# KeypadConnection.net
KiCad netlist of a schematic drawn in Altium Designer
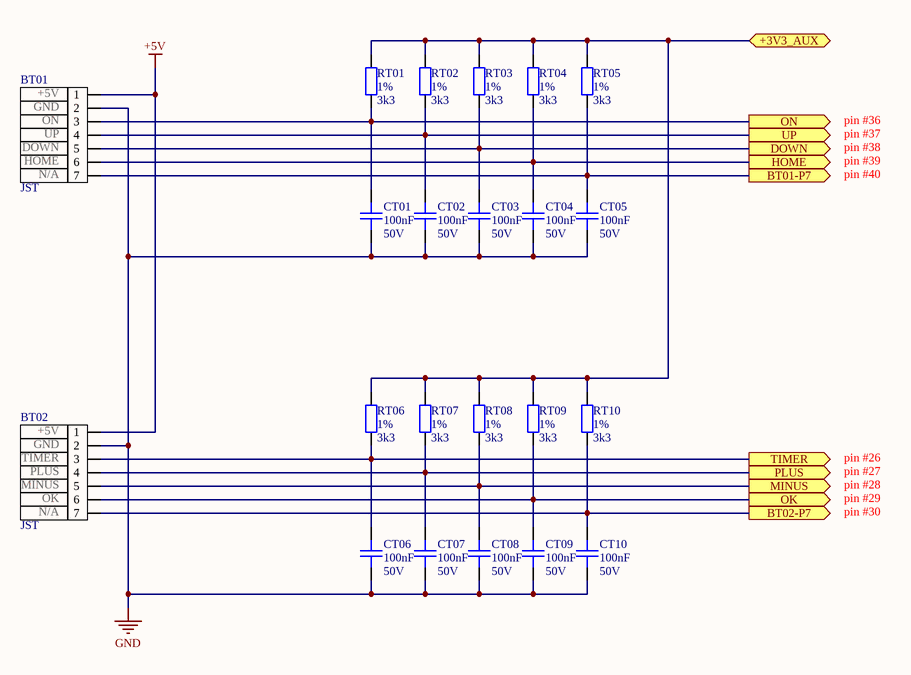
[diagram p0: KeypadConnection.SchDoc]

(export (version "E")
  (design (tool "Eeschema 10.0.6"))
  (components
    (comp (ref "BT01")
      (value "JST")
      (fields
        (field (name "PIN_1") "+5V")
        (field (name "PIN_2") "GND")
        (field (name "PIN_3") "ON")
        (field (name "PIN_4") "UP")
        (field (name "PIN_5") "DOWN")
        (field (name "PIN_6") "HOME")
        (field (name "PIN_7") "N/A")
      )
      (libsource (lib "connectors_ffc") (part "CONN FFC 7POS 1MM"))
    )
    (comp (ref "BT02")
      (value "JST")
      (fields
        (field (name "PIN_1") "+5V")
        (field (name "PIN_2") "GND")
        (field (name "PIN_3") "TIMER")
        (field (name "PIN_4") "PLUS")
        (field (name "PIN_5") "MINUS")
        (field (name "PIN_6") "OK")
        (field (name "PIN_7") "N/A")
      )
      (libsource (lib "connectors_ffc") (part "CONN FFC 7POS 1MM"))
    )
    (comp (ref "CT01")
      (value "CAP CER 0.1uF ±10% 50V X7R 0603")
      (footprint "CAPC1608X08N_0603")
      (description "Capacitor")
      (fields
        (field (name "MANUFACTURER") "KEMET")
        (field (name "MANUFACTURER PART NUMBER") "C0603C104M5RACTU")
        (field (name "CAPACITANCE") "100nF")
        (field (name "VOLTAGE RATING") "50V")
      )
      (libsource (lib "capacitors_smd") (part "CAP CER 0.1uF ±10% 50V X7R 0603"))
    )
    (comp (ref "CT02")
      (value "CAP CER 0.1uF ±10% 50V X7R 0603")
      (footprint "CAPC1608X08N_0603")
      (description "Capacitor")
      (fields
        (field (name "MANUFACTURER") "KEMET")
        (field (name "MANUFACTURER PART NUMBER") "C0603C104M5RACTU")
        (field (name "CAPACITANCE") "100nF")
        (field (name "VOLTAGE RATING") "50V")
      )
      (libsource (lib "capacitors_smd") (part "CAP CER 0.1uF ±10% 50V X7R 0603"))
    )
    (comp (ref "CT03")
      (value "CAP CER 0.1uF ±10% 50V X7R 0603")
      (footprint "CAPC1608X08N_0603")
      (description "Capacitor")
      (fields
        (field (name "MANUFACTURER") "KEMET")
        (field (name "MANUFACTURER PART NUMBER") "C0603C104M5RACTU")
        (field (name "CAPACITANCE") "100nF")
        (field (name "VOLTAGE RATING") "50V")
      )
      (libsource (lib "capacitors_smd") (part "CAP CER 0.1uF ±10% 50V X7R 0603"))
    )
    (comp (ref "CT04")
      (value "CAP CER 0.1uF ±10% 50V X7R 0603")
      (footprint "CAPC1608X08N_0603")
      (description "Capacitor")
      (fields
        (field (name "MANUFACTURER") "KEMET")
        (field (name "MANUFACTURER PART NUMBER") "C0603C104M5RACTU")
        (field (name "CAPACITANCE") "100nF")
        (field (name "VOLTAGE RATING") "50V")
      )
      (libsource (lib "capacitors_smd") (part "CAP CER 0.1uF ±10% 50V X7R 0603"))
    )
    (comp (ref "CT05")
      (value "CAP CER 0.1uF ±10% 50V X7R 0603")
      (footprint "CAPC1608X08N_0603")
      (description "Capacitor")
      (fields
        (field (name "MANUFACTURER") "KEMET")
        (field (name "MANUFACTURER PART NUMBER") "C0603C104M5RACTU")
        (field (name "CAPACITANCE") "100nF")
        (field (name "VOLTAGE RATING") "50V")
      )
      (libsource (lib "capacitors_smd") (part "CAP CER 0.1uF ±10% 50V X7R 0603"))
    )
    (comp (ref "CT06")
      (value "CAP CER 0.1uF ±10% 50V X7R 0603")
      (footprint "CAPC1608X08N_0603")
      (description "Capacitor")
      (fields
        (field (name "MANUFACTURER") "KEMET")
        (field (name "MANUFACTURER PART NUMBER") "C0603C104M5RACTU")
        (field (name "CAPACITANCE") "100nF")
        (field (name "VOLTAGE RATING") "50V")
      )
      (libsource (lib "capacitors_smd") (part "CAP CER 0.1uF ±10% 50V X7R 0603"))
    )
    (comp (ref "CT07")
      (value "CAP CER 0.1uF ±10% 50V X7R 0603")
      (footprint "CAPC1608X08N_0603")
      (description "Capacitor")
      (fields
        (field (name "MANUFACTURER") "KEMET")
        (field (name "MANUFACTURER PART NUMBER") "C0603C104M5RACTU")
        (field (name "CAPACITANCE") "100nF")
        (field (name "VOLTAGE RATING") "50V")
      )
      (libsource (lib "capacitors_smd") (part "CAP CER 0.1uF ±10% 50V X7R 0603"))
    )
    (comp (ref "CT08")
      (value "CAP CER 0.1uF ±10% 50V X7R 0603")
      (footprint "CAPC1608X08N_0603")
      (description "Capacitor")
      (fields
        (field (name "MANUFACTURER") "KEMET")
        (field (name "MANUFACTURER PART NUMBER") "C0603C104M5RACTU")
        (field (name "CAPACITANCE") "100nF")
        (field (name "VOLTAGE RATING") "50V")
      )
      (libsource (lib "capacitors_smd") (part "CAP CER 0.1uF ±10% 50V X7R 0603"))
    )
    (comp (ref "CT09")
      (value "CAP CER 0.1uF ±10% 50V X7R 0603")
      (footprint "CAPC1608X08N_0603")
      (description "Capacitor")
      (fields
        (field (name "MANUFACTURER") "KEMET")
        (field (name "MANUFACTURER PART NUMBER") "C0603C104M5RACTU")
        (field (name "CAPACITANCE") "100nF")
        (field (name "VOLTAGE RATING") "50V")
      )
      (libsource (lib "capacitors_smd") (part "CAP CER 0.1uF ±10% 50V X7R 0603"))
    )
    (comp (ref "CT10")
      (value "CAP CER 0.1uF ±10% 50V X7R 0603")
      (footprint "CAPC1608X08N_0603")
      (description "Capacitor")
      (fields
        (field (name "MANUFACTURER") "KEMET")
        (field (name "MANUFACTURER PART NUMBER") "C0603C104M5RACTU")
        (field (name "CAPACITANCE") "100nF")
        (field (name "VOLTAGE RATING") "50V")
      )
      (libsource (lib "capacitors_smd") (part "CAP CER 0.1uF ±10% 50V X7R 0603"))
    )
    (comp (ref "RT01")
      (value "R 3kΩ ±1% 0603 0.1W")
      (footprint "Resistor-0603")
      (description "Resistor")
      (fields
        (field (name "MANUFACTURER") "Yageo")
        (field (name "MANUFACTURER PART NUMBER") "RC0603FR-073KL")
        (field (name "TOLERANCE") "1%")
        (field (name "RESISTANCE") "3k3")
      )
      (libsource (lib "resistors_smd") (part "R 3kΩ ±1% 0603 0.1W"))
    )
    (comp (ref "RT02")
      (value "R 3kΩ ±1% 0603 0.1W")
      (footprint "Resistor-0603")
      (description "Resistor")
      (fields
        (field (name "MANUFACTURER") "Yageo")
        (field (name "MANUFACTURER PART NUMBER") "RC0603FR-073KL")
        (field (name "TOLERANCE") "1%")
        (field (name "RESISTANCE") "3k3")
      )
      (libsource (lib "resistors_smd") (part "R 3kΩ ±1% 0603 0.1W"))
    )
    (comp (ref "RT03")
      (value "R 3kΩ ±1% 0603 0.1W")
      (footprint "Resistor-0603")
      (description "Resistor")
      (fields
        (field (name "MANUFACTURER") "Yageo")
        (field (name "MANUFACTURER PART NUMBER") "RC0603FR-073KL")
        (field (name "TOLERANCE") "1%")
        (field (name "RESISTANCE") "3k3")
      )
      (libsource (lib "resistors_smd") (part "R 3kΩ ±1% 0603 0.1W"))
    )
    (comp (ref "RT04")
      (value "R 3kΩ ±1% 0603 0.1W")
      (footprint "Resistor-0603")
      (description "Resistor")
      (fields
        (field (name "MANUFACTURER") "Yageo")
        (field (name "MANUFACTURER PART NUMBER") "RC0603FR-073KL")
        (field (name "TOLERANCE") "1%")
        (field (name "RESISTANCE") "3k3")
      )
      (libsource (lib "resistors_smd") (part "R 3kΩ ±1% 0603 0.1W"))
    )
    (comp (ref "RT05")
      (value "R 3kΩ ±1% 0603 0.1W")
      (footprint "Resistor-0603")
      (description "Resistor")
      (fields
        (field (name "MANUFACTURER") "Yageo")
        (field (name "MANUFACTURER PART NUMBER") "RC0603FR-073KL")
        (field (name "TOLERANCE") "1%")
        (field (name "RESISTANCE") "3k3")
      )
      (libsource (lib "resistors_smd") (part "R 3kΩ ±1% 0603 0.1W"))
    )
    (comp (ref "RT06")
      (value "R 3kΩ ±1% 0603 0.1W")
      (footprint "Resistor-0603")
      (description "Resistor")
      (fields
        (field (name "MANUFACTURER") "Yageo")
        (field (name "MANUFACTURER PART NUMBER") "RC0603FR-073KL")
        (field (name "TOLERANCE") "1%")
        (field (name "RESISTANCE") "3k3")
      )
      (libsource (lib "resistors_smd") (part "R 3kΩ ±1% 0603 0.1W"))
    )
    (comp (ref "RT07")
      (value "R 3kΩ ±1% 0603 0.1W")
      (footprint "Resistor-0603")
      (description "Resistor")
      (fields
        (field (name "MANUFACTURER") "Yageo")
        (field (name "MANUFACTURER PART NUMBER") "RC0603FR-073KL")
        (field (name "TOLERANCE") "1%")
        (field (name "RESISTANCE") "3k3")
      )
      (libsource (lib "resistors_smd") (part "R 3kΩ ±1% 0603 0.1W"))
    )
    (comp (ref "RT08")
      (value "R 3kΩ ±1% 0603 0.1W")
      (footprint "Resistor-0603")
      (description "Resistor")
      (fields
        (field (name "MANUFACTURER") "Yageo")
        (field (name "MANUFACTURER PART NUMBER") "RC0603FR-073KL")
        (field (name "TOLERANCE") "1%")
        (field (name "RESISTANCE") "3k3")
      )
      (libsource (lib "resistors_smd") (part "R 3kΩ ±1% 0603 0.1W"))
    )
    (comp (ref "RT09")
      (value "R 3kΩ ±1% 0603 0.1W")
      (footprint "Resistor-0603")
      (description "Resistor")
      (fields
        (field (name "MANUFACTURER") "Yageo")
        (field (name "MANUFACTURER PART NUMBER") "RC0603FR-073KL")
        (field (name "TOLERANCE") "1%")
        (field (name "RESISTANCE") "3k3")
      )
      (libsource (lib "resistors_smd") (part "R 3kΩ ±1% 0603 0.1W"))
    )
    (comp (ref "RT10")
      (value "R 3kΩ ±1% 0603 0.1W")
      (footprint "Resistor-0603")
      (description "Resistor")
      (fields
        (field (name "MANUFACTURER") "Yageo")
        (field (name "MANUFACTURER PART NUMBER") "RC0603FR-073KL")
        (field (name "TOLERANCE") "1%")
        (field (name "RESISTANCE") "3k3")
      )
      (libsource (lib "resistors_smd") (part "R 3kΩ ±1% 0603 0.1W"))
    )
  )
  (nets
    (net (code "1") (name "+5V") (class "Default")
      (node (ref "BT01") (pin "1") (pinfunction "1_1") (pintype "passive"))
      (node (ref "BT02") (pin "1") (pinfunction "1_1") (pintype "passive"))
    )
    (net (code "2") (name "/+3V3_AUX") (class "Default")
      (node (ref "RT01") (pin "2") (pinfunction "2_2") (pintype "passive"))
      (node (ref "RT02") (pin "2") (pinfunction "2_2") (pintype "passive"))
      (node (ref "RT03") (pin "2") (pinfunction "2_2") (pintype "passive"))
      (node (ref "RT04") (pin "2") (pinfunction "2_2") (pintype "passive"))
      (node (ref "RT05") (pin "2") (pinfunction "2_2") (pintype "passive"))
      (node (ref "RT06") (pin "2") (pinfunction "2_2") (pintype "passive"))
      (node (ref "RT07") (pin "2") (pinfunction "2_2") (pintype "passive"))
      (node (ref "RT08") (pin "2") (pinfunction "2_2") (pintype "passive"))
      (node (ref "RT09") (pin "2") (pinfunction "2_2") (pintype "passive"))
      (node (ref "RT10") (pin "2") (pinfunction "2_2") (pintype "passive"))
    )
    (net (code "3") (name "/BT01-P7") (class "Default")
      (node (ref "BT01") (pin "7") (pinfunction "7_7") (pintype "passive"))
      (node (ref "CT05") (pin "2") (pinfunction "2_2") (pintype "passive"))
      (node (ref "RT05") (pin "1") (pinfunction "1_1") (pintype "passive"))
    )
    (net (code "4") (name "/BT02-P7") (class "Default")
      (node (ref "BT02") (pin "7") (pinfunction "7_7") (pintype "passive"))
      (node (ref "CT10") (pin "2") (pinfunction "2_2") (pintype "passive"))
      (node (ref "RT10") (pin "1") (pinfunction "1_1") (pintype "passive"))
    )
    (net (code "5") (name "/DOWN") (class "Default")
      (node (ref "BT01") (pin "5") (pinfunction "5_5") (pintype "passive"))
      (node (ref "CT03") (pin "2") (pinfunction "2_2") (pintype "passive"))
      (node (ref "RT03") (pin "1") (pinfunction "1_1") (pintype "passive"))
    )
    (net (code "6") (name "/HOME") (class "Default")
      (node (ref "BT01") (pin "6") (pinfunction "6_6") (pintype "passive"))
      (node (ref "CT04") (pin "2") (pinfunction "2_2") (pintype "passive"))
      (node (ref "RT04") (pin "1") (pinfunction "1_1") (pintype "passive"))
    )
    (net (code "7") (name "/MINUS") (class "Default")
      (node (ref "BT02") (pin "5") (pinfunction "5_5") (pintype "passive"))
      (node (ref "CT08") (pin "2") (pinfunction "2_2") (pintype "passive"))
      (node (ref "RT08") (pin "1") (pinfunction "1_1") (pintype "passive"))
    )
    (net (code "8") (name "/OK") (class "Default")
      (node (ref "BT02") (pin "6") (pinfunction "6_6") (pintype "passive"))
      (node (ref "CT09") (pin "2") (pinfunction "2_2") (pintype "passive"))
      (node (ref "RT09") (pin "1") (pinfunction "1_1") (pintype "passive"))
    )
    (net (code "9") (name "/ON") (class "Default")
      (node (ref "BT01") (pin "3") (pinfunction "3_3") (pintype "passive"))
      (node (ref "CT01") (pin "2") (pinfunction "2_2") (pintype "passive"))
      (node (ref "RT01") (pin "1") (pinfunction "1_1") (pintype "passive"))
    )
    (net (code "10") (name "/PLUS") (class "Default")
      (node (ref "BT02") (pin "4") (pinfunction "4_4") (pintype "passive"))
      (node (ref "CT07") (pin "2") (pinfunction "2_2") (pintype "passive"))
      (node (ref "RT07") (pin "1") (pinfunction "1_1") (pintype "passive"))
    )
    (net (code "11") (name "/TIMER") (class "Default")
      (node (ref "BT02") (pin "3") (pinfunction "3_3") (pintype "passive"))
      (node (ref "CT06") (pin "2") (pinfunction "2_2") (pintype "passive"))
      (node (ref "RT06") (pin "1") (pinfunction "1_1") (pintype "passive"))
    )
    (net (code "12") (name "/UP") (class "Default")
      (node (ref "BT01") (pin "4") (pinfunction "4_4") (pintype "passive"))
      (node (ref "CT02") (pin "2") (pinfunction "2_2") (pintype "passive"))
      (node (ref "RT02") (pin "1") (pinfunction "1_1") (pintype "passive"))
    )
    (net (code "13") (name "GND") (class "Default")
      (node (ref "BT01") (pin "2") (pinfunction "2_2") (pintype "passive"))
      (node (ref "BT02") (pin "2") (pinfunction "2_2") (pintype "passive"))
      (node (ref "CT01") (pin "1") (pinfunction "1_1") (pintype "passive"))
      (node (ref "CT02") (pin "1") (pinfunction "1_1") (pintype "passive"))
      (node (ref "CT03") (pin "1") (pinfunction "1_1") (pintype "passive"))
      (node (ref "CT04") (pin "1") (pinfunction "1_1") (pintype "passive"))
      (node (ref "CT05") (pin "1") (pinfunction "1_1") (pintype "passive"))
      (node (ref "CT06") (pin "1") (pinfunction "1_1") (pintype "passive"))
      (node (ref "CT07") (pin "1") (pinfunction "1_1") (pintype "passive"))
      (node (ref "CT08") (pin "1") (pinfunction "1_1") (pintype "passive"))
      (node (ref "CT09") (pin "1") (pinfunction "1_1") (pintype "passive"))
      (node (ref "CT10") (pin "1") (pinfunction "1_1") (pintype "passive"))
    )
  )
)
